# MotorEncoder.net
KiCad netlist of a schematic drawn in EAGLE
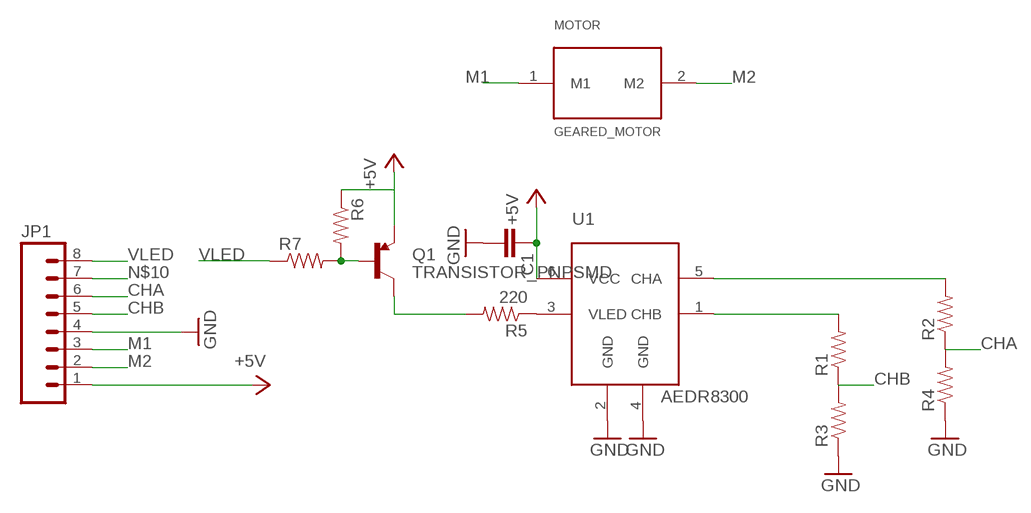
[diagram p0: schematic, sheet 1]

(export (version "E")
  (design (tool "Eeschema 10.0.6"))
  (components
    (comp (ref "C1")
      (value "CAP0603-CAP")
      (footprint "eagle-import:0603-CAP")
      (libsource (lib "eagle-import") (part "CAP0603-CAP"))
    )
    (comp (ref "JP1")
      (value "M08BM08B-SRSS-TB")
      (footprint "eagle-import:BM08B-SRSS-TB")
      (libsource (lib "eagle-import") (part "M08BM08B-SRSS-TB"))
    )
    (comp (ref "MOTOR")
      (value "GEARED_MOTOR")
      (footprint "eagle-import:GEARED_MOTOR")
      (libsource (lib "eagle-import") (part "GEARED_MOTOR"))
    )
    (comp (ref "Q1")
      (value "TRANSISTOR_PNPSMD")
      (footprint "eagle-import:SOT23-3")
      (libsource (lib "eagle-import") (part "TRANSISTOR_PNPSMD"))
    )
    (comp (ref "R1")
      (value "RESISTOR0603-RES")
      (footprint "eagle-import:0603-RES")
      (libsource (lib "eagle-import") (part "RESISTOR0603-RES"))
    )
    (comp (ref "R2")
      (value "RESISTOR0603-RES")
      (footprint "eagle-import:0603-RES")
      (libsource (lib "eagle-import") (part "RESISTOR0603-RES"))
    )
    (comp (ref "R3")
      (value "RESISTOR0603-RES")
      (footprint "eagle-import:0603-RES")
      (libsource (lib "eagle-import") (part "RESISTOR0603-RES"))
    )
    (comp (ref "R4")
      (value "RESISTOR0603-RES")
      (footprint "eagle-import:0603-RES")
      (libsource (lib "eagle-import") (part "RESISTOR0603-RES"))
    )
    (comp (ref "R5")
      (value "220")
      (footprint "eagle-import:0603-RES")
      (libsource (lib "eagle-import") (part "RESISTOR0603-RES"))
    )
    (comp (ref "R6")
      (value "RESISTOR0603-RES")
      (footprint "eagle-import:0603-RES")
      (libsource (lib "eagle-import") (part "RESISTOR0603-RES"))
    )
    (comp (ref "R7")
      (value "RESISTOR0603-RES")
      (footprint "eagle-import:0603-RES")
      (libsource (lib "eagle-import") (part "RESISTOR0603-RES"))
    )
    (comp (ref "U1")
      (value "AEDR8300")
      (footprint "eagle-import:AEDR8300")
      (libsource (lib "eagle-import") (part "AEDR8300"))
    )
  )
  (nets
    (net (code "1") (name "+5V") (class "Default")
      (node (ref "C1") (pin "1") (pinfunction "1_1") (pintype "passive"))
      (node (ref "JP1") (pin "1") (pinfunction "1_1") (pintype "passive"))
      (node (ref "Q1") (pin "2") (pinfunction "E_2") (pintype "passive"))
      (node (ref "R6") (pin "1") (pinfunction "1_1") (pintype "passive"))
      (node (ref "U1") (pin "6") (pinfunction "VCC_6") (pintype "bidirectional"))
    )
    (net (code "2") (name "/CHA") (class "Default")
      (node (ref "JP1") (pin "6") (pinfunction "6_6") (pintype "passive"))
      (node (ref "R2") (pin "1") (pinfunction "1_1") (pintype "passive"))
      (node (ref "R4") (pin "2") (pinfunction "2_2") (pintype "passive"))
    )
    (net (code "3") (name "/CHB") (class "Default")
      (node (ref "JP1") (pin "5") (pinfunction "5_5") (pintype "passive"))
      (node (ref "R1") (pin "1") (pinfunction "1_1") (pintype "passive"))
      (node (ref "R3") (pin "2") (pinfunction "2_2") (pintype "passive"))
    )
    (net (code "4") (name "/M1") (class "Default")
      (node (ref "JP1") (pin "3") (pinfunction "3_3") (pintype "passive"))
      (node (ref "MOTOR") (pin "1") (pinfunction "M1_1") (pintype "bidirectional"))
    )
    (net (code "5") (name "/M2") (class "Default")
      (node (ref "JP1") (pin "2") (pinfunction "2_2") (pintype "passive"))
      (node (ref "MOTOR") (pin "2") (pinfunction "M2_2") (pintype "bidirectional"))
    )
    (net (code "6") (name "/N$10") (class "Default")
      (node (ref "JP1") (pin "7") (pinfunction "7_7") (pintype "passive"))
    )
    (net (code "7") (name "/VLED") (class "Default")
      (node (ref "JP1") (pin "8") (pinfunction "8_8") (pintype "passive"))
      (node (ref "R7") (pin "1") (pinfunction "1_1") (pintype "passive"))
    )
    (net (code "8") (name "GND") (class "Default")
      (node (ref "C1") (pin "2") (pinfunction "2_2") (pintype "passive"))
      (node (ref "JP1") (pin "4") (pinfunction "4_4") (pintype "passive"))
      (node (ref "R3") (pin "1") (pinfunction "1_1") (pintype "passive"))
      (node (ref "R4") (pin "1") (pinfunction "1_1") (pintype "passive"))
      (node (ref "U1") (pin "2") (pinfunction "GND_2") (pintype "bidirectional"))
      (node (ref "U1") (pin "4") (pinfunction "GND_4") (pintype "bidirectional"))
    )
    (net (code "9") (name "Net-(Q1-B)") (class "Default")
      (node (ref "Q1") (pin "1") (pinfunction "B_1") (pintype "passive"))
      (node (ref "R6") (pin "2") (pinfunction "2_2") (pintype "passive"))
      (node (ref "R7") (pin "2") (pinfunction "2_2") (pintype "passive"))
    )
    (net (code "10") (name "Net-(Q1-C)") (class "Default")
      (node (ref "Q1") (pin "3") (pinfunction "C_3") (pintype "passive"))
      (node (ref "R5") (pin "2") (pinfunction "2_2") (pintype "passive"))
    )
    (net (code "11") (name "Net-(U1-CHA)") (class "Default")
      (node (ref "R2") (pin "2") (pinfunction "2_2") (pintype "passive"))
      (node (ref "U1") (pin "5") (pinfunction "CHA_5") (pintype "bidirectional"))
    )
    (net (code "12") (name "Net-(U1-CHB)") (class "Default")
      (node (ref "R1") (pin "2") (pinfunction "2_2") (pintype "passive"))
      (node (ref "U1") (pin "1") (pinfunction "CHB_1") (pintype "bidirectional"))
    )
    (net (code "13") (name "Net-(U1-VLED)") (class "Default")
      (node (ref "R5") (pin "1") (pinfunction "1_1") (pintype "passive"))
      (node (ref "U1") (pin "3") (pinfunction "VLED_3") (pintype "bidirectional"))
    )
  )
)
